# ChameleonMini-RevG.net
KiCad netlist of a schematic drawn in EAGLE
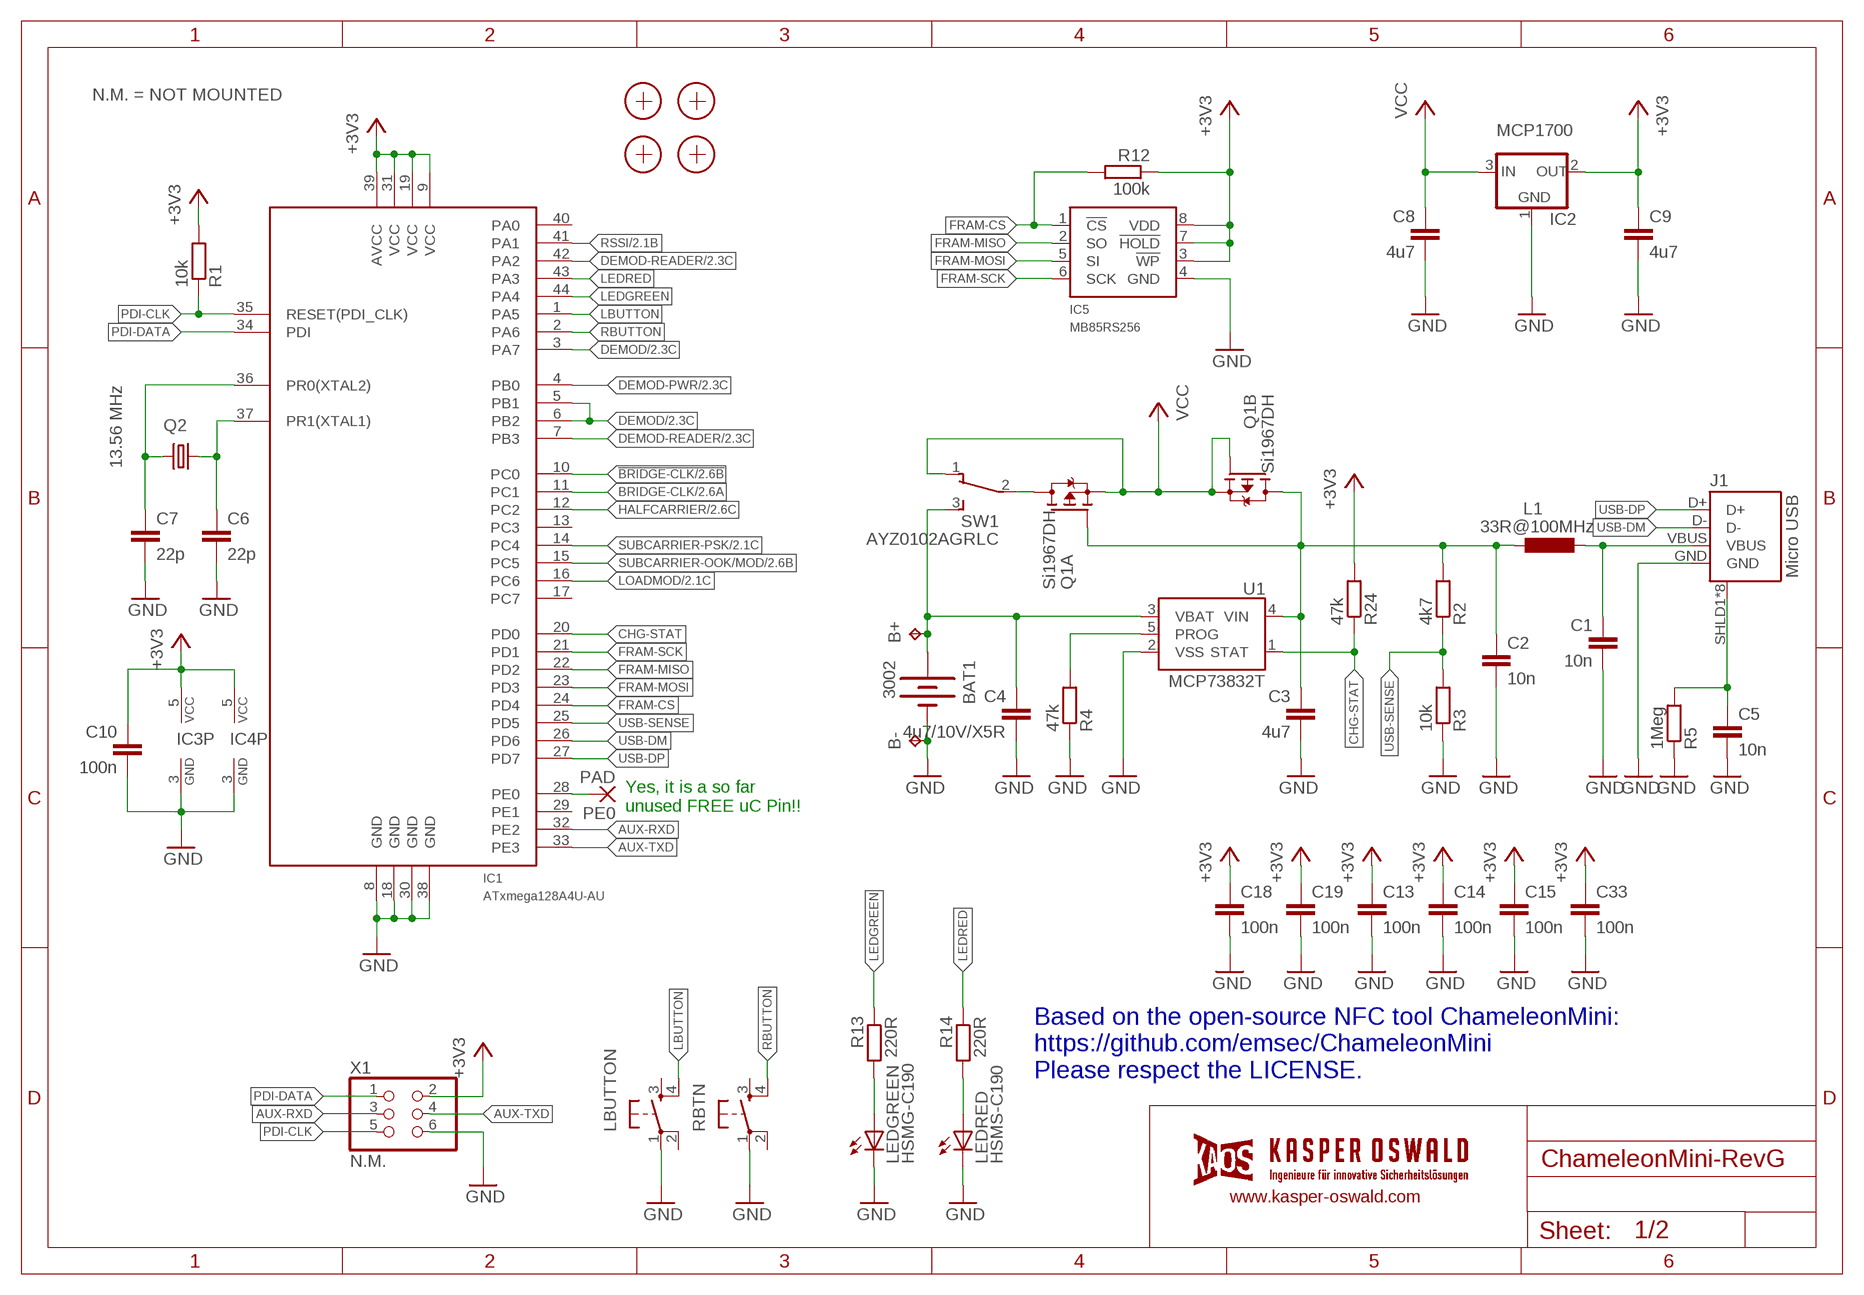
[diagram p0: schematic, sheet 1]
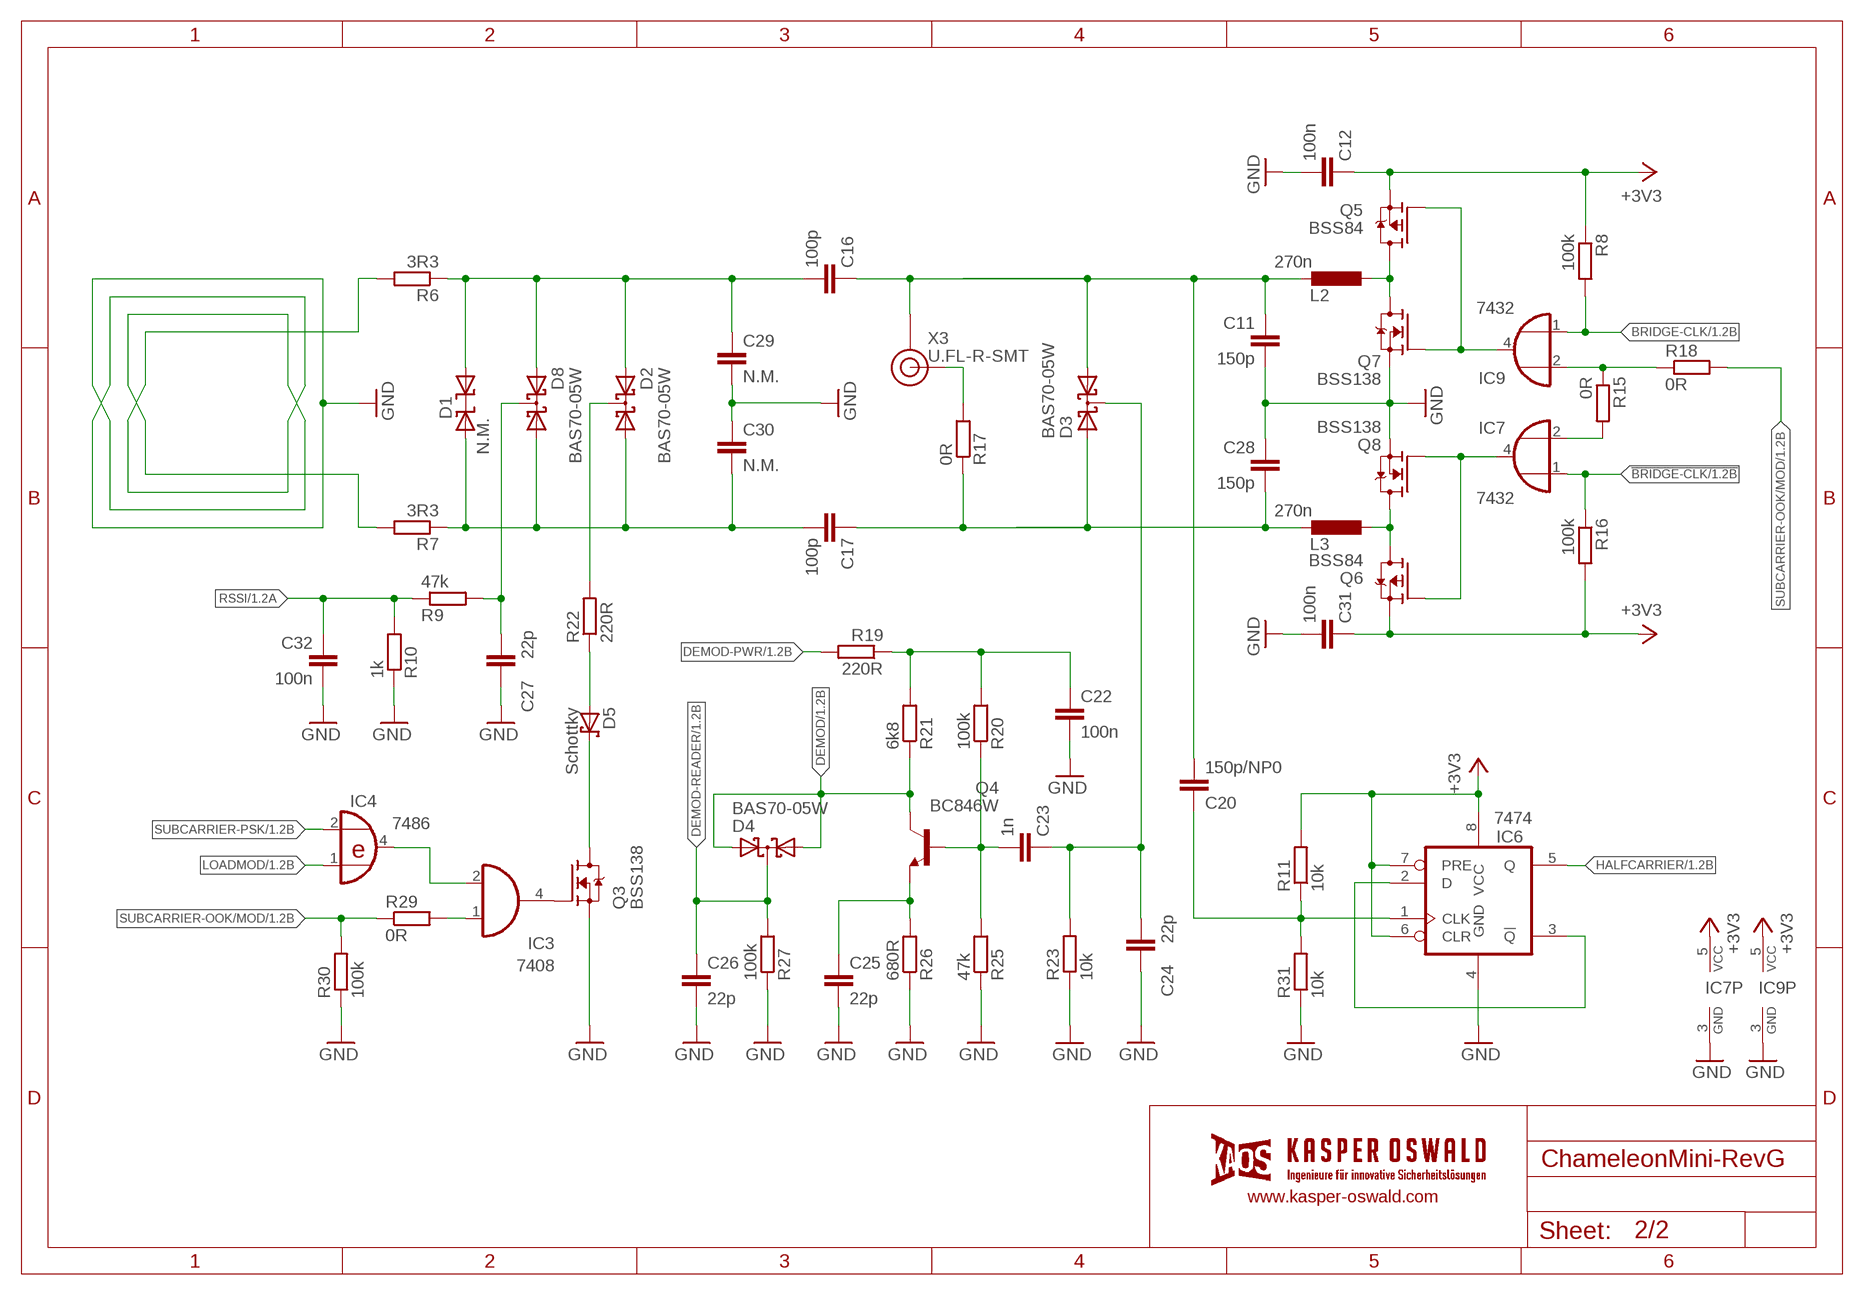
[diagram p1: schematic, sheet 2]

(export (version "E")
  (design (tool "Eeschema 10.0.6"))
  (components
    (comp (ref "C11")
      (value "150p")
      (footprint "eagle-import:C0603K")
      (libsource (lib "eagle-import") (part "C-EUC0603K"))
    )
    (comp (ref "C12")
      (value "100n")
      (footprint "eagle-import:C0603K")
      (libsource (lib "eagle-import") (part "C-EUC0603K"))
    )
    (comp (ref "C16")
      (value "100p")
      (footprint "eagle-import:C0603K")
      (libsource (lib "eagle-import") (part "C-EUC0603K"))
    )
    (comp (ref "C17")
      (value "100p")
      (footprint "eagle-import:C0603K")
      (libsource (lib "eagle-import") (part "C-EUC0603K"))
    )
    (comp (ref "C20")
      (value "150p/NP0")
      (footprint "eagle-import:C0603K")
      (libsource (lib "eagle-import") (part "C-EUC0603K"))
    )
    (comp (ref "C22")
      (value "100n")
      (footprint "eagle-import:C0603K")
      (libsource (lib "eagle-import") (part "C-EUC0603K"))
    )
    (comp (ref "C23")
      (value "1n")
      (footprint "eagle-import:C0603K")
      (libsource (lib "eagle-import") (part "C-EUC0603K"))
    )
    (comp (ref "C24")
      (value "22p")
      (footprint "eagle-import:C0603K")
      (libsource (lib "eagle-import") (part "C-EUC0603K"))
    )
    (comp (ref "C25")
      (value "22p")
      (footprint "eagle-import:C0603K")
      (libsource (lib "eagle-import") (part "C-EUC0603K"))
    )
    (comp (ref "C26")
      (value "22p")
      (footprint "eagle-import:C0603K")
      (libsource (lib "eagle-import") (part "C-EUC0603K"))
    )
    (comp (ref "C27")
      (value "22p")
      (footprint "eagle-import:C0603K")
      (libsource (lib "eagle-import") (part "C-EUC0603K"))
    )
    (comp (ref "C28")
      (value "150p")
      (footprint "eagle-import:C0603K")
      (libsource (lib "eagle-import") (part "C-EUC0603K"))
    )
    (comp (ref "C29")
      (value "N.M.")
      (footprint "eagle-import:C0603K")
      (libsource (lib "eagle-import") (part "C-EUC0603K"))
    )
    (comp (ref "C30")
      (value "N.M.")
      (footprint "eagle-import:C0603K")
      (libsource (lib "eagle-import") (part "C-EUC0603K"))
    )
    (comp (ref "C31")
      (value "100n")
      (footprint "eagle-import:C0603K")
      (libsource (lib "eagle-import") (part "C-EUC0603K"))
    )
    (comp (ref "C32")
      (value "100n")
      (footprint "eagle-import:C0603K")
      (libsource (lib "eagle-import") (part "C-EUC0603K"))
    )
    (comp (ref "D1")
      (value "N.M.")
      (footprint "eagle-import:DO214AC")
      (libsource (lib "eagle-import") (part "SMAJ"))
    )
    (comp (ref "D2")
      (value "BAS70-05W")
      (footprint "eagle-import:SOT323")
      (libsource (lib "eagle-import") (part "BAS70-05W"))
    )
    (comp (ref "D3")
      (value "BAS70-05W")
      (footprint "eagle-import:SOT323")
      (libsource (lib "eagle-import") (part "BAS70-05W"))
    )
    (comp (ref "D4")
      (value "BAS70-05W")
      (footprint "eagle-import:SOT323")
      (libsource (lib "eagle-import") (part "BAS70-05W"))
    )
    (comp (ref "D5")
      (value "Schottky")
      (footprint "eagle-import:SOD323(F)")
      (libsource (lib "eagle-import") (part "1PS76SB70"))
    )
    (comp (ref "D8")
      (value "BAS70-05W")
      (footprint "eagle-import:SOT323")
      (libsource (lib "eagle-import") (part "BAS70-05W"))
    )
    (comp (ref "IC3")
      (value "7408")
      (footprint "eagle-import:SC70-5")
      (libsource (lib "eagle-import") (part "741G08DCKLVC"))
    )
    (comp (ref "IC4")
      (value "7486")
      (footprint "eagle-import:SC70-5")
      (libsource (lib "eagle-import") (part "741G86DCKAHC"))
    )
    (comp (ref "IC6")
      (value "7474")
      (footprint "eagle-import:VSSOP8")
      (libsource (lib "eagle-import") (part "74LVC1G74DC"))
    )
    (comp (ref "IC7")
      (value "7432")
      (footprint "eagle-import:SC70-5")
      (libsource (lib "eagle-import") (part "741G32DCKAHC"))
    )
    (comp (ref "IC9")
      (value "7432")
      (footprint "eagle-import:SC70-5")
      (libsource (lib "eagle-import") (part "741G32DCKAHC"))
    )
    (comp (ref "L2")
      (value "270n")
      (footprint "eagle-import:L2012C")
      (libsource (lib "eagle-import") (part "L-EUL2012C"))
    )
    (comp (ref "L3")
      (value "270n")
      (footprint "eagle-import:L2012C")
      (libsource (lib "eagle-import") (part "L-EUL2012C"))
    )
    (comp (ref "Q3")
      (value "BSS138")
      (footprint "eagle-import:SOT323")
      (libsource (lib "eagle-import") (part "BSS138BKW"))
    )
    (comp (ref "Q4")
      (value "BC846W")
      (footprint "eagle-import:SOT323")
      (libsource (lib "eagle-import") (part "BC84XW"))
    )
    (comp (ref "Q5")
      (value "BSS84")
      (footprint "eagle-import:SOT323")
      (libsource (lib "eagle-import") (part "BSS84AKW"))
    )
    (comp (ref "Q6")
      (value "BSS84")
      (footprint "eagle-import:SOT323")
      (libsource (lib "eagle-import") (part "BSS84AKW"))
    )
    (comp (ref "Q7")
      (value "BSS138")
      (footprint "eagle-import:SOT323")
      (libsource (lib "eagle-import") (part "BSS138BKW"))
    )
    (comp (ref "Q8")
      (value "BSS138")
      (footprint "eagle-import:SOT323")
      (libsource (lib "eagle-import") (part "BSS138BKW"))
    )
    (comp (ref "R6")
      (value "3R3")
      (footprint "eagle-import:R0603")
      (libsource (lib "eagle-import") (part "R-EU_R0603"))
    )
    (comp (ref "R7")
      (value "3R3")
      (footprint "eagle-import:R0603")
      (libsource (lib "eagle-import") (part "R-EU_R0603"))
    )
    (comp (ref "R8")
      (value "100k")
      (footprint "eagle-import:R0603")
      (libsource (lib "eagle-import") (part "R-EU_R0603"))
    )
    (comp (ref "R9")
      (value "47k")
      (footprint "eagle-import:R0603")
      (libsource (lib "eagle-import") (part "R-EU_R0603"))
    )
    (comp (ref "R10")
      (value "1k")
      (footprint "eagle-import:R0603")
      (libsource (lib "eagle-import") (part "R-EU_R0603"))
    )
    (comp (ref "R11")
      (value "10k")
      (footprint "eagle-import:R0603")
      (libsource (lib "eagle-import") (part "R-EU_R0603"))
    )
    (comp (ref "R15")
      (value "0R")
      (footprint "eagle-import:R0603")
      (libsource (lib "eagle-import") (part "R-EU_R0603"))
    )
    (comp (ref "R16")
      (value "100k")
      (footprint "eagle-import:R0603")
      (libsource (lib "eagle-import") (part "R-EU_R0603"))
    )
    (comp (ref "R17")
      (value "0R")
      (footprint "eagle-import:R0603")
      (libsource (lib "eagle-import") (part "R-EU_R0603"))
    )
    (comp (ref "R18")
      (value "0R")
      (footprint "eagle-import:R0603")
      (libsource (lib "eagle-import") (part "R-EU_R0603"))
    )
    (comp (ref "R19")
      (value "220R")
      (footprint "eagle-import:R0603")
      (libsource (lib "eagle-import") (part "R-EU_R0603"))
    )
    (comp (ref "R20")
      (value "100k")
      (footprint "eagle-import:R0603")
      (libsource (lib "eagle-import") (part "R-EU_R0603"))
    )
    (comp (ref "R21")
      (value "6k8")
      (footprint "eagle-import:R0603")
      (libsource (lib "eagle-import") (part "R-EU_R0603"))
    )
    (comp (ref "R22")
      (value "220R")
      (footprint "eagle-import:R0603")
      (libsource (lib "eagle-import") (part "R-EU_R0603"))
    )
    (comp (ref "R23")
      (value "10k")
      (footprint "eagle-import:R0603")
      (libsource (lib "eagle-import") (part "R-EU_R0603"))
    )
    (comp (ref "R25")
      (value "47k")
      (footprint "eagle-import:R0603")
      (libsource (lib "eagle-import") (part "R-EU_R0603"))
    )
    (comp (ref "R26")
      (value "680R")
      (footprint "eagle-import:R0603")
      (libsource (lib "eagle-import") (part "R-EU_R0603"))
    )
    (comp (ref "R27")
      (value "100k")
      (footprint "eagle-import:R0603")
      (libsource (lib "eagle-import") (part "R-EU_R0603"))
    )
    (comp (ref "R29")
      (value "0R")
      (footprint "eagle-import:R0603")
      (libsource (lib "eagle-import") (part "R-EU_R0603"))
    )
    (comp (ref "R30")
      (value "100k")
      (footprint "eagle-import:R0603")
      (libsource (lib "eagle-import") (part "R-EU_R0603"))
    )
    (comp (ref "R31")
      (value "10k")
      (footprint "eagle-import:R0603")
      (libsource (lib "eagle-import") (part "R-EU_R0603"))
    )
    (comp (ref "X3")
      (value "U.FL-R-SMT")
      (footprint "eagle-import:U.FL-R-SMT")
      (libsource (lib "eagle-import") (part "U.FL-R-SMT"))
    )
    (comp (ref "B+")
      (value "TPTP18SQ")
      (footprint "eagle-import:TP18SQ")
      (libsource (lib "eagle-import") (part "TPTP18SQ"))
    )
    (comp (ref "B-")
      (value "TPTP18SQ")
      (footprint "eagle-import:TP18SQ")
      (libsource (lib "eagle-import") (part "TPTP18SQ"))
    )
    (comp (ref "BAT1")
      (value "3002")
      (footprint "eagle-import:BATTCON_20MM")
      (libsource (lib "eagle-import") (part "3002"))
    )
    (comp (ref "C1")
      (value "10n")
      (footprint "eagle-import:C1206K")
      (libsource (lib "eagle-import") (part "C-EUC1206K"))
    )
    (comp (ref "C2")
      (value "10n")
      (footprint "eagle-import:C1206K")
      (libsource (lib "eagle-import") (part "C-EUC1206K"))
    )
    (comp (ref "C3")
      (value "4u7")
      (footprint "eagle-import:C0603K")
      (libsource (lib "eagle-import") (part "C-EUC0603K"))
    )
    (comp (ref "C4")
      (value "4u7/10V/X5R")
      (footprint "eagle-import:C0603K")
      (libsource (lib "eagle-import") (part "C-EUC0603K"))
    )
    (comp (ref "C5")
      (value "10n")
      (footprint "eagle-import:C0603K")
      (libsource (lib "eagle-import") (part "C-EUC0603K"))
    )
    (comp (ref "C6")
      (value "22p")
      (footprint "eagle-import:C0603K")
      (libsource (lib "eagle-import") (part "C-EUC0603K"))
    )
    (comp (ref "C7")
      (value "22p")
      (footprint "eagle-import:C0603K")
      (libsource (lib "eagle-import") (part "C-EUC0603K"))
    )
    (comp (ref "C8")
      (value "4u7")
      (footprint "eagle-import:C0603K")
      (libsource (lib "eagle-import") (part "C-EUC0603K"))
    )
    (comp (ref "C9")
      (value "4u7")
      (footprint "eagle-import:C0603K")
      (libsource (lib "eagle-import") (part "C-EUC0603K"))
    )
    (comp (ref "C10")
      (value "100n")
      (footprint "eagle-import:C0603K")
      (libsource (lib "eagle-import") (part "C-EUC0603K"))
    )
    (comp (ref "C13")
      (value "100n")
      (footprint "eagle-import:C0603K")
      (libsource (lib "eagle-import") (part "C-EUC0603K"))
    )
    (comp (ref "C14")
      (value "100n")
      (footprint "eagle-import:C0603K")
      (libsource (lib "eagle-import") (part "C-EUC0603K"))
    )
    (comp (ref "C15")
      (value "100n")
      (footprint "eagle-import:C0603K")
      (libsource (lib "eagle-import") (part "C-EUC0603K"))
    )
    (comp (ref "C18")
      (value "100n")
      (footprint "eagle-import:C0603K")
      (libsource (lib "eagle-import") (part "C-EUC0603K"))
    )
    (comp (ref "C19")
      (value "100n")
      (footprint "eagle-import:C0603K")
      (libsource (lib "eagle-import") (part "C-EUC0603K"))
    )
    (comp (ref "C33")
      (value "100n")
      (footprint "eagle-import:C0603K")
      (libsource (lib "eagle-import") (part "C-EUC0603K"))
    )
    (comp (ref "IC1")
      (value "ATxmega128A4U-AU")
      (footprint "eagle-import:TQFP44")
      (libsource (lib "eagle-import") (part "ATXMEGA_A4-A"))
    )
    (comp (ref "IC2")
      (value "MCP1700")
      (footprint "eagle-import:SOT23")
      (libsource (lib "eagle-import") (part "MCP1702"))
    )
    (comp (ref "IC5")
      (value "MB85RS256")
      (footprint "eagle-import:SO-08")
      (libsource (lib "eagle-import") (part "MB85RS"))
    )
    (comp (ref "J1")
      (value "Micro USB")
      (footprint "eagle-import:USB-MICROB-10118194")
      (libsource (lib "eagle-import") (part "USB-MICROB-2"))
    )
    (comp (ref "L1")
      (value "33R@100MHz")
      (footprint "eagle-import:L2012C")
      (libsource (lib "eagle-import") (part "L-EUL2012C"))
    )
    (comp (ref "LBUTTON")
      (value "SWITCH_SPST_4_PINSQUARE")
      (footprint "eagle-import:TACTILE-SWITCH-SMD")
      (libsource (lib "eagle-import") (part "SWITCH_SPST_4_PINSQUARE"))
    )
    (comp (ref "LEDGREEN")
      (value "HSMG-C190")
      (footprint "eagle-import:CHIPLED-0603")
      (libsource (lib "eagle-import") (part "LED-0603"))
    )
    (comp (ref "LEDRED")
      (value "HSMS-C190")
      (footprint "eagle-import:CHIPLED-0603")
      (libsource (lib "eagle-import") (part "LED-0603"))
    )
    (comp (ref "PE0")
      (value "PAD")
      (footprint "eagle-import:SMD1,27-2,54")
      (libsource (lib "eagle-import") (part "WIREPADSMD1,27-254"))
    )
    (comp (ref "Q1")
      (value "Si1967DH")
      (footprint "eagle-import:SOT363")
      (libsource (lib "eagle-import") (part "BSS84AKS"))
    )
    (comp (ref "Q2")
      (value "13.56 MHz")
      (footprint "eagle-import:5MMX3.2MM")
      (libsource (lib "eagle-import") (part "TXC7B"))
    )
    (comp (ref "R1")
      (value "10k")
      (footprint "eagle-import:R0603")
      (libsource (lib "eagle-import") (part "R-EU_R0603"))
    )
    (comp (ref "R2")
      (value "4k7")
      (footprint "eagle-import:R0603")
      (libsource (lib "eagle-import") (part "R-EU_R0603"))
    )
    (comp (ref "R3")
      (value "10k")
      (footprint "eagle-import:R0603")
      (libsource (lib "eagle-import") (part "R-EU_R0603"))
    )
    (comp (ref "R4")
      (value "47k")
      (footprint "eagle-import:R0603")
      (libsource (lib "eagle-import") (part "R-EU_R0603"))
    )
    (comp (ref "R5")
      (value "1Meg")
      (footprint "eagle-import:R0603")
      (libsource (lib "eagle-import") (part "R-EU_R0603"))
    )
    (comp (ref "R12")
      (value "100k")
      (footprint "eagle-import:R0603")
      (libsource (lib "eagle-import") (part "R-EU_R0603"))
    )
    (comp (ref "R13")
      (value "220R")
      (footprint "eagle-import:R0603")
      (libsource (lib "eagle-import") (part "R-EU_R0603"))
    )
    (comp (ref "R14")
      (value "220R")
      (footprint "eagle-import:R0603")
      (libsource (lib "eagle-import") (part "R-EU_R0603"))
    )
    (comp (ref "R24")
      (value "47k")
      (footprint "eagle-import:R0603")
      (libsource (lib "eagle-import") (part "R-EU_R0603"))
    )
    (comp (ref "RBTN")
      (value "SWITCH_SPST_4_PINSQUARE")
      (footprint "eagle-import:TACTILE-SWITCH-SMD")
      (libsource (lib "eagle-import") (part "SWITCH_SPST_4_PINSQUARE"))
    )
    (comp (ref "SW1")
      (value "AYZ0102AGRLC")
      (footprint "eagle-import:AYZ0102AGRLC")
      (libsource (lib "eagle-import") (part "AYZ0102AGRLC"))
    )
    (comp (ref "U1")
      (value "MCP73832T")
      (footprint "eagle-import:SOT23-5")
      (libsource (lib "eagle-import") (part "MCP73831"))
    )
    (comp (ref "X1")
      (value "N.M.")
      (footprint "eagle-import:PINHD-2X3-2.54-EDGE")
      (libsource (lib "eagle-import") (part "PINHD-2X3-2.54-EDGE"))
    )
    (comp (ref "X2")
      (value "PASSER-07")
      (footprint "eagle-import:PASSER_07MM")
      (libsource (lib "eagle-import") (part "PASSER-07"))
    )
    (comp (ref "X4")
      (value "PASSER-07")
      (footprint "eagle-import:PASSER_07MM")
      (libsource (lib "eagle-import") (part "PASSER-07"))
    )
    (comp (ref "X5")
      (value "PASSER-07")
      (footprint "eagle-import:PASSER_07MM")
      (libsource (lib "eagle-import") (part "PASSER-07"))
    )
    (comp (ref "X6")
      (value "PASSER-07")
      (footprint "eagle-import:PASSER_07MM")
      (libsource (lib "eagle-import") (part "PASSER-07"))
    )
  )
  (nets
    (net (code "1") (name "+3V3") (class "Default")
      (node (ref "C10") (pin "1") (pinfunction "1_1") (pintype "passive"))
      (node (ref "C12") (pin "1") (pinfunction "1_1") (pintype "passive"))
      (node (ref "C13") (pin "1") (pinfunction "1_1") (pintype "passive"))
      (node (ref "C14") (pin "1") (pinfunction "1_1") (pintype "passive"))
      (node (ref "C15") (pin "1") (pinfunction "1_1") (pintype "passive"))
      (node (ref "C18") (pin "1") (pinfunction "1_1") (pintype "passive"))
      (node (ref "C19") (pin "1") (pinfunction "1_1") (pintype "passive"))
      (node (ref "C31") (pin "1") (pinfunction "1_1") (pintype "passive"))
      (node (ref "C33") (pin "1") (pinfunction "1_1") (pintype "passive"))
      (node (ref "C9") (pin "1") (pinfunction "1_1") (pintype "passive"))
      (node (ref "IC1") (pin "19") (pinfunction "VCC_19") (pintype "bidirectional"))
      (node (ref "IC1") (pin "31") (pinfunction "VCC_31") (pintype "bidirectional"))
      (node (ref "IC1") (pin "39") (pinfunction "AVCC_39") (pintype "bidirectional"))
      (node (ref "IC1") (pin "9") (pinfunction "VCC_9") (pintype "bidirectional"))
      (node (ref "IC2") (pin "2") (pinfunction "OUT_2") (pintype "passive"))
      (node (ref "IC3") (pin "5") (pinfunction "VCC_5") (pintype "power_in"))
      (node (ref "IC4") (pin "5") (pinfunction "VCC_5") (pintype "power_in"))
      (node (ref "IC5") (pin "3") (pinfunction "~{WP}_3") (pintype "bidirectional"))
      (node (ref "IC5") (pin "7") (pinfunction "~{HOLD}_7") (pintype "bidirectional"))
      (node (ref "IC5") (pin "8") (pinfunction "VDD_8") (pintype "bidirectional"))
      (node (ref "IC6") (pin "6") (pinfunction "CLR_6") (pintype "input"))
      (node (ref "IC6") (pin "7") (pinfunction "PRE_7") (pintype "input"))
      (node (ref "IC6") (pin "8") (pinfunction "VCC_8") (pintype "bidirectional"))
      (node (ref "IC7") (pin "5") (pinfunction "VCC_5") (pintype "power_in"))
      (node (ref "IC9") (pin "5") (pinfunction "VCC_5") (pintype "power_in"))
      (node (ref "Q5") (pin "2") (pinfunction "S_2") (pintype "passive"))
      (node (ref "Q6") (pin "2") (pinfunction "S_2") (pintype "passive"))
      (node (ref "R1") (pin "2") (pinfunction "2_2") (pintype "passive"))
      (node (ref "R11") (pin "2") (pinfunction "2_2") (pintype "passive"))
      (node (ref "R12") (pin "1") (pinfunction "1_1") (pintype "passive"))
      (node (ref "R16") (pin "2") (pinfunction "2_2") (pintype "passive"))
      (node (ref "R24") (pin "2") (pinfunction "2_2") (pintype "passive"))
      (node (ref "R8") (pin "1") (pinfunction "1_1") (pintype "passive"))
      (node (ref "X1") (pin "2") (pinfunction "2_2") (pintype "passive"))
    )
    (net (code "2") (name "AUX-RXD") (class "Default")
      (node (ref "IC1") (pin "32") (pinfunction "PE2_32") (pintype "bidirectional"))
      (node (ref "X1") (pin "3") (pinfunction "3_3") (pintype "passive"))
    )
    (net (code "3") (name "AUX-TXD") (class "Default")
      (node (ref "IC1") (pin "33") (pinfunction "PE3_33") (pintype "bidirectional"))
      (node (ref "X1") (pin "4") (pinfunction "4_4") (pintype "passive"))
    )
    (net (code "4") (name "BRIDGE-CLK") (class "Default")
      (node (ref "IC1") (pin "11") (pinfunction "PC1_11") (pintype "bidirectional"))
      (node (ref "IC9") (pin "1") (pinfunction "I0_1") (pintype "input"))
      (node (ref "R8") (pin "2") (pinfunction "2_2") (pintype "passive"))
    )
    (net (code "5") (name "CHG-STAT") (class "Default")
      (node (ref "IC1") (pin "20") (pinfunction "PD0_20") (pintype "bidirectional"))
      (node (ref "R24") (pin "1") (pinfunction "1_1") (pintype "passive"))
      (node (ref "U1") (pin "1") (pinfunction "STAT_1") (pintype "output"))
    )
    (net (code "6") (name "DEMOD") (class "Default")
      (node (ref "D4") (pin "1") (pinfunction "A1_1") (pintype "passive"))
      (node (ref "D4") (pin "2") (pinfunction "A2_2") (pintype "passive"))
      (node (ref "IC1") (pin "3") (pinfunction "PA7_3") (pintype "bidirectional"))
      (node (ref "IC1") (pin "5") (pinfunction "PB1_5") (pintype "bidirectional"))
      (node (ref "IC1") (pin "6") (pinfunction "PB2_6") (pintype "bidirectional"))
      (node (ref "Q4") (pin "3") (pinfunction "C_3") (pintype "passive"))
      (node (ref "R21") (pin "1") (pinfunction "1_1") (pintype "passive"))
    )
    (net (code "7") (name "DEMOD-PWR") (class "Default")
      (node (ref "IC1") (pin "4") (pinfunction "PB0_4") (pintype "bidirectional"))
      (node (ref "R19") (pin "2") (pinfunction "2_2") (pintype "passive"))
    )
    (net (code "8") (name "DEMOD-READER") (class "Default")
      (node (ref "C26") (pin "1") (pinfunction "1_1") (pintype "passive"))
      (node (ref "D4") (pin "3") (pinfunction "K_3") (pintype "passive"))
      (node (ref "IC1") (pin "42") (pinfunction "PA2_42") (pintype "bidirectional"))
      (node (ref "IC1") (pin "7") (pinfunction "PB3_7") (pintype "bidirectional"))
      (node (ref "R27") (pin "2") (pinfunction "2_2") (pintype "passive"))
    )
    (net (code "9") (name "FRAM-CS") (class "Default")
      (node (ref "IC1") (pin "24") (pinfunction "PD4_24") (pintype "bidirectional"))
      (node (ref "IC5") (pin "1") (pinfunction "~{CS}_1") (pintype "bidirectional"))
      (node (ref "R12") (pin "2") (pinfunction "2_2") (pintype "passive"))
    )
    (net (code "10") (name "FRAM-MISO") (class "Default")
      (node (ref "IC1") (pin "22") (pinfunction "PD2_22") (pintype "bidirectional"))
      (node (ref "IC5") (pin "2") (pinfunction "SO_2") (pintype "bidirectional"))
    )
    (net (code "11") (name "FRAM-MOSI") (class "Default")
      (node (ref "IC1") (pin "23") (pinfunction "PD3_23") (pintype "bidirectional"))
      (node (ref "IC5") (pin "5") (pinfunction "SI_5") (pintype "bidirectional"))
    )
    (net (code "12") (name "FRAM-SCK") (class "Default")
      (node (ref "IC1") (pin "21") (pinfunction "PD1_21") (pintype "bidirectional"))
      (node (ref "IC5") (pin "6") (pinfunction "SCK_6") (pintype "bidirectional"))
    )
    (net (code "13") (name "GND") (class "Default")
      (node (ref "B-") (pin "TP") (pinfunction "TP_TP") (pintype "input"))
      (node (ref "BAT1") (pin "-") (pinfunction "-_-") (pintype "power_in"))
      (node (ref "C1") (pin "2") (pinfunction "2_2") (pintype "passive"))
      (node (ref "C10") (pin "2") (pinfunction "2_2") (pintype "passive"))
      (node (ref "C11") (pin "2") (pinfunction "2_2") (pintype "passive"))
      (node (ref "C12") (pin "2") (pinfunction "2_2") (pintype "passive"))
      (node (ref "C13") (pin "2") (pinfunction "2_2") (pintype "passive"))
      (node (ref "C14") (pin "2") (pinfunction "2_2") (pintype "passive"))
      (node (ref "C15") (pin "2") (pinfunction "2_2") (pintype "passive"))
      (node (ref "C18") (pin "2") (pinfunction "2_2") (pintype "passive"))
      (node (ref "C19") (pin "2") (pinfunction "2_2") (pintype "passive"))
      (node (ref "C2") (pin "2") (pinfunction "2_2") (pintype "passive"))
      (node (ref "C22") (pin "2") (pinfunction "2_2") (pintype "passive"))
      (node (ref "C24") (pin "2") (pinfunction "2_2") (pintype "passive"))
      (node (ref "C25") (pin "2") (pinfunction "2_2") (pintype "passive"))
      (node (ref "C26") (pin "2") (pinfunction "2_2") (pintype "passive"))
      (node (ref "C27") (pin "2") (pinfunction "2_2") (pintype "passive"))
      (node (ref "C28") (pin "1") (pinfunction "1_1") (pintype "passive"))
      (node (ref "C29") (pin "2") (pinfunction "2_2") (pintype "passive"))
      (node (ref "C3") (pin "2") (pinfunction "2_2") (pintype "passive"))
      (node (ref "C30") (pin "1") (pinfunction "1_1") (pintype "passive"))
      (node (ref "C31") (pin "2") (pinfunction "2_2") (pintype "passive"))
      (node (ref "C32") (pin "2") (pinfunction "2_2") (pintype "passive"))
      (node (ref "C33") (pin "2") (pinfunction "2_2") (pintype "passive"))
      (node (ref "C4") (pin "2") (pinfunction "2_2") (pintype "passive"))
      (node (ref "C5") (pin "2") (pinfunction "2_2") (pintype "passive"))
      (node (ref "C6") (pin "2") (pinfunction "2_2") (pintype "passive"))
      (node (ref "C7") (pin "2") (pinfunction "2_2") (pintype "passive"))
      (node (ref "C8") (pin "2") (pinfunction "2_2") (pintype "passive"))
      (node (ref "C9") (pin "2") (pinfunction "2_2") (pintype "passive"))
      (node (ref "IC1") (pin "18") (pinfunction "GND_18") (pintype "bidirectional"))
      (node (ref "IC1") (pin "30") (pinfunction "GND_30") (pintype "bidirectional"))
      (node (ref "IC1") (pin "38") (pinfunction "GND_38") (pintype "bidirectional"))
      (node (ref "IC1") (pin "8") (pinfunction "GND_8") (pintype "bidirectional"))
      (node (ref "IC2") (pin "1") (pinfunction "GND_1") (pintype "input"))
      (node (ref "IC3") (pin "3") (pinfunction "GND_3") (pintype "power_in"))
      (node (ref "IC4") (pin "3") (pinfunction "GND_3") (pintype "power_in"))
      (node (ref "IC5") (pin "4") (pinfunction "GND_4") (pintype "bidirectional"))
      (node (ref "IC6") (pin "4") (pinfunction "GND_4") (pintype "bidirectional"))
      (node (ref "IC7") (pin "3") (pinfunction "GND_3") (pintype "power_in"))
      (node (ref "IC9") (pin "3") (pinfunction "GND_3") (pintype "power_in"))
      (node (ref "J1") (pin "GND") (pinfunction "GND_GND") (pintype "power_in"))
      (node (ref "LBUTTON") (pin "1") (pinfunction "1_1") (pintype "passive"))
      (node (ref "LEDGREEN") (pin "C") (pinfunction "C_C") (pintype "passive"))
      (node (ref "LEDRED") (pin "C") (pinfunction "C_C") (pintype "passive"))
      (node (ref "Q3") (pin "2") (pinfunction "S_2") (pintype "passive"))
      (node (ref "Q7") (pin "2") (pinfunction "S_2") (pintype "passive"))
      (node (ref "Q8") (pin "2") (pinfunction "S_2") (pintype "passive"))
      (node (ref "R10") (pin "1") (pinfunction "1_1") (pintype "passive"))
      (node (ref "R23") (pin "1") (pinfunction "1_1") (pintype "passive"))
      (node (ref "R25") (pin "1") (pinfunction "1_1") (pintype "passive"))
      (node (ref "R26") (pin "1") (pinfunction "1_1") (pintype "passive"))
      (node (ref "R27") (pin "1") (pinfunction "1_1") (pintype "passive"))
      (node (ref "R3") (pin "1") (pinfunction "1_1") (pintype "passive"))
      (node (ref "R30") (pin "1") (pinfunction "1_1") (pintype "passive"))
      (node (ref "R31") (pin "1") (pinfunction "1_1") (pintype "passive"))
      (node (ref "R4") (pin "1") (pinfunction "1_1") (pintype "passive"))
      (node (ref "R5") (pin "1") (pinfunction "1_1") (pintype "passive"))
      (node (ref "R6") (pin "2") (pinfunction "2_2") (pintype "passive"))
      (node (ref "R7") (pin "2") (pinfunction "2_2") (pintype "passive"))
      (node (ref "RBTN") (pin "1") (pinfunction "1_1") (pintype "passive"))
      (node (ref "U1") (pin "2") (pinfunction "VSS_2") (pintype "power_in"))
      (node (ref "X1") (pin "6") (pinfunction "6_6") (pintype "passive"))
    )
    (net (code "14") (name "HALFCARRIER") (class "Default")
      (node (ref "IC1") (pin "12") (pinfunction "PC2_12") (pintype "bidirectional"))
      (node (ref "IC6") (pin "5") (pinfunction "Q_5") (pintype "output"))
    )
    (net (code "15") (name "LBUTTON") (class "Default")
      (node (ref "IC1") (pin "1") (pinfunction "PA5_1") (pintype "bidirectional"))
      (node (ref "LBUTTON") (pin "4") (pinfunction "4_4") (pintype "passive"))
    )
    (net (code "16") (name "LEDGREEN") (class "Default")
      (node (ref "IC1") (pin "44") (pinfunction "PA4_44") (pintype "bidirectional"))
      (node (ref "R13") (pin "1") (pinfunction "1_1") (pintype "passive"))
    )
    (net (code "17") (name "LEDRED") (class "Default")
      (node (ref "IC1") (pin "43") (pinfunction "PA3_43") (pintype "bidirectional"))
      (node (ref "R14") (pin "1") (pinfunction "1_1") (pintype "passive"))
    )
    (net (code "18") (name "LOADMOD") (class "Default")
      (node (ref "IC1") (pin "16") (pinfunction "PC6_16") (pintype "bidirectional"))
      (node (ref "IC4") (pin "1") (pinfunction "I0_1") (pintype "input"))
    )
    (net (code "19") (name "Net-(BAT1-+)") (class "Default")
      (node (ref "B+") (pin "TP") (pinfunction "TP_TP") (pintype "input"))
      (node (ref "BAT1") (pin "+2") (pinfunction "+_+2") (pintype "power_in"))
      (node (ref "C4") (pin "1") (pinfunction "1_1") (pintype "passive"))
      (node (ref "SW1") (pin "3") (pinfunction "S_3") (pintype "passive"))
      (node (ref "U1") (pin "3") (pinfunction "VBAT_3") (pintype "power_in"))
    )
    (net (code "20") (name "Net-(C1-Pad1)") (class "Default")
      (node (ref "C1") (pin "1") (pinfunction "1_1") (pintype "passive"))
      (node (ref "J1") (pin "VBUS") (pinfunction "VBUS_VBUS") (pintype "power_in"))
      (node (ref "L1") (pin "1") (pinfunction "1_1") (pintype "passive"))
    )
    (net (code "21") (name "Net-(C5-Pad1)") (class "Default")
      (node (ref "C5") (pin "1") (pinfunction "1_1") (pintype "passive"))
      (node (ref "J1") (pin "SHLD1") (pinfunction "SHIELD_SHLD1") (pintype "passive"))
      (node (ref "J1") (pin "SHLD2") (pinfunction "SHIELD_SHLD2") (pintype "passive"))
      (node (ref "J1") (pin "SHLD3") (pinfunction "SHIELD_SHLD3") (pintype "passive"))
      (node (ref "J1") (pin "SHLD4") (pinfunction "SHIELD_SHLD4") (pintype "passive"))
      (node (ref "J1") (pin "SHLD5") (pinfunction "SHIELD_SHLD5") (pintype "passive"))
      (node (ref "J1") (pin "SHLD6") (pinfunction "SHIELD_SHLD6") (pintype "passive"))
      (node (ref "J1") (pin "SHLD7") (pinfunction "SHIELD_SHLD7") (pintype "passive"))
      (node (ref "J1") (pin "SHLD8") (pinfunction "SHIELD_SHLD8") (pintype "passive"))
      (node (ref "R5") (pin "2") (pinfunction "2_2") (pintype "passive"))
    )
    (net (code "22") (name "Net-(C22-Pad1)") (class "Default")
      (node (ref "C22") (pin "1") (pinfunction "1_1") (pintype "passive"))
      (node (ref "R19") (pin "1") (pinfunction "1_1") (pintype "passive"))
      (node (ref "R20") (pin "2") (pinfunction "2_2") (pintype "passive"))
      (node (ref "R21") (pin "2") (pinfunction "2_2") (pintype "passive"))
    )
    (net (code "23") (name "Net-(D2-A1)") (class "Default")
      (node (ref "C16") (pin "2") (pinfunction "2_2") (pintype "passive"))
      (node (ref "C29") (pin "1") (pinfunction "1_1") (pintype "passive"))
      (node (ref "D1") (pin "2") (pinfunction "2_2") (pintype "passive"))
      (node (ref "D2") (pin "1") (pinfunction "A1_1") (pintype "passive"))
      (node (ref "D8") (pin "1") (pinfunction "A1_1") (pintype "passive"))
      (node (ref "R6") (pin "1") (pinfunction "1_1") (pintype "passive"))
    )
    (net (code "24") (name "Net-(D2-A2)") (class "Default")
      (node (ref "C17") (pin "2") (pinfunction "2_2") (pintype "passive"))
      (node (ref "C30") (pin "2") (pinfunction "2_2") (pintype "passive"))
      (node (ref "D1") (pin "1") (pinfunction "1_1") (pintype "passive"))
      (node (ref "D2") (pin "2") (pinfunction "A2_2") (pintype "passive"))
      (node (ref "D8") (pin "2") (pinfunction "A2_2") (pintype "passive"))
      (node (ref "R7") (pin "1") (pinfunction "1_1") (pintype "passive"))
    )
    (net (code "25") (name "Net-(D2-K)") (class "Default")
      (node (ref "D2") (pin "3") (pinfunction "K_3") (pintype "passive"))
      (node (ref "R22") (pin "2") (pinfunction "2_2") (pintype "passive"))
    )
    (net (code "26") (name "Net-(D3-A1)") (class "Default")
      (node (ref "C17") (pin "1") (pinfunction "1_1") (pintype "passive"))
      (node (ref "C28") (pin "2") (pinfunction "2_2") (pintype "passive"))
      (node (ref "D3") (pin "1") (pinfunction "A1_1") (pintype "passive"))
      (node (ref "L3") (pin "2") (pinfunction "2_2") (pintype "passive"))
      (node (ref "R17") (pin "1") (pinfunction "1_1") (pintype "passive"))
    )
    (net (code "27") (name "Net-(D3-A2)") (class "Default")
      (node (ref "C11") (pin "1") (pinfunction "1_1") (pintype "passive"))
      (node (ref "C16") (pin "1") (pinfunction "1_1") (pintype "passive"))
      (node (ref "C20") (pin "2") (pinfunction "2_2") (pintype "passive"))
      (node (ref "D3") (pin "2") (pinfunction "A2_2") (pintype "passive"))
      (node (ref "L2") (pin "2") (pinfunction "2_2") (pintype "passive"))
      (node (ref "X3") (pin "GND1") (pinfunction "GND_GND1") (pintype "bidirectional"))
    )
    (net (code "28") (name "Net-(D3-K)") (class "Default")
      (node (ref "C23") (pin "1") (pinfunction "1_1") (pintype "passive"))
      (node (ref "C24") (pin "1") (pinfunction "1_1") (pintype "passive"))
      (node (ref "D3") (pin "3") (pinfunction "K_3") (pintype "passive"))
      (node (ref "R23") (pin "2") (pinfunction "2_2") (pintype "passive"))
    )
    (net (code "29") (name "Net-(D5-A)") (class "Default")
      (node (ref "D5") (pin "2") (pinfunction "A_2") (pintype "passive"))
      (node (ref "R22") (pin "1") (pinfunction "1_1") (pintype "passive"))
    )
    (net (code "30") (name "Net-(D5-K)") (class "Default")
      (node (ref "D5") (pin "1") (pinfunction "K_1") (pintype "passive"))
      (node (ref "Q3") (pin "3") (pinfunction "D_3") (pintype "passive"))
    )
    (net (code "31") (name "Net-(D8-K)") (class "Default")
      (node (ref "C27") (pin "1") (pinfunction "1_1") (pintype "passive"))
      (node (ref "D8") (pin "3") (pinfunction "K_3") (pintype "passive"))
      (node (ref "R9") (pin "2") (pinfunction "2_2") (pintype "passive"))
    )
    (net (code "32") (name "Net-(IC1-PE0)") (class "Default")
      (node (ref "IC1") (pin "28") (pinfunction "PE0_28") (pintype "bidirectional"))
      (node (ref "PE0") (pin "1") (pinfunction "P_1") (pintype "passive"))
    )
    (net (code "33") (name "Net-(IC1-PR0(XTAL2))") (class "Default")
      (node (ref "C7") (pin "1") (pinfunction "1_1") (pintype "passive"))
      (node (ref "IC1") (pin "36") (pinfunction "PR0(XTAL2)_36") (pintype "bidirectional"))
      (node (ref "Q2") (pin "3") (pinfunction "2_3") (pintype "passive"))
    )
    (net (code "34") (name "Net-(IC1-PR1(XTAL1))") (class "Default")
      (node (ref "C6") (pin "1") (pinfunction "1_1") (pintype "passive"))
      (node (ref "IC1") (pin "37") (pinfunction "PR1(XTAL1)_37") (pintype "bidirectional"))
      (node (ref "Q2") (pin "1") (pinfunction "1_1") (pintype "passive"))
    )
    (net (code "35") (name "Net-(IC3A-I0)") (class "Default")
      (node (ref "IC3") (pin "1") (pinfunction "I0_1") (pintype "input"))
      (node (ref "R29") (pin "2") (pinfunction "2_2") (pintype "passive"))
    )
    (net (code "36") (name "Net-(IC3A-I1)") (class "Default")
      (node (ref "IC3") (pin "2") (pinfunction "I1_2") (pintype "input"))
      (node (ref "IC4") (pin "4") (pinfunction "O_4") (pintype "output"))
    )
    (net (code "37") (name "Net-(IC3A-O)") (class "Default")
      (node (ref "IC3") (pin "4") (pinfunction "O_4") (pintype "output"))
      (node (ref "Q3") (pin "1") (pinfunction "G_1") (pintype "passive"))
    )
    (net (code "38") (name "Net-(IC6-CLK)") (class "Default")
      (node (ref "C20") (pin "1") (pinfunction "1_1") (pintype "passive"))
      (node (ref "IC6") (pin "1") (pinfunction "CLK_1") (pintype "input"))
      (node (ref "R11") (pin "1") (pinfunction "1_1") (pintype "passive"))
      (node (ref "R31") (pin "2") (pinfunction "2_2") (pintype "passive"))
    )
    (net (code "39") (name "Net-(IC6-D)") (class "Default")
      (node (ref "IC6") (pin "2") (pinfunction "D_2") (pintype "input"))
      (node (ref "IC6") (pin "3") (pinfunction "~{Q}_3") (pintype "output"))
    )
    (net (code "40") (name "Net-(IC7A-I1)") (class "Default")
      (node (ref "IC7") (pin "2") (pinfunction "I1_2") (pintype "input"))
      (node (ref "R15") (pin "2") (pinfunction "2_2") (pintype "passive"))
    )
    (net (code "41") (name "Net-(IC7A-O)") (class "Default")
      (node (ref "IC7") (pin "4") (pinfunction "O_4") (pintype "output"))
      (node (ref "Q6") (pin "1") (pinfunction "G_1") (pintype "passive"))
      (node (ref "Q8") (pin "1") (pinfunction "G_1") (pintype "passive"))
    )
    (net (code "42") (name "Net-(IC9A-I1)") (class "Default")
      (node (ref "IC9") (pin "2") (pinfunction "I1_2") (pintype "input"))
      (node (ref "R15") (pin "1") (pinfunction "1_1") (pintype "passive"))
      (node (ref "R18") (pin "1") (pinfunction "1_1") (pintype "passive"))
    )
    (net (code "43") (name "Net-(IC9A-O)") (class "Default")
      (node (ref "IC9") (pin "4") (pinfunction "O_4") (pintype "output"))
      (node (ref "Q5") (pin "1") (pinfunction "G_1") (pintype "passive"))
      (node (ref "Q7") (pin "1") (pinfunction "G_1") (pintype "passive"))
    )
    (net (code "44") (name "Net-(LEDGREEN-PadA)") (class "Default")
      (node (ref "LEDGREEN") (pin "A") (pinfunction "A_A") (pintype "passive"))
      (node (ref "R13") (pin "2") (pinfunction "2_2") (pintype "passive"))
    )
    (net (code "45") (name "Net-(LEDRED-PadA)") (class "Default")
      (node (ref "LEDRED") (pin "A") (pinfunction "A_A") (pintype "passive"))
      (node (ref "R14") (pin "2") (pinfunction "2_2") (pintype "passive"))
    )
    (net (code "46") (name "Net-(Q1A-D)") (class "Default")
      (node (ref "Q1") (pin "6") (pinfunction "D_6") (pintype "passive"))
      (node (ref "SW1") (pin "2") (pinfunction "P_2") (pintype "passive"))
    )
    (net (code "47") (name "Net-(Q1A-G)") (class "Default")
      (node (ref "C2") (pin "1") (pinfunction "1_1") (pintype "passive"))
      (node (ref "C3") (pin "1") (pinfunction "1_1") (pintype "passive"))
      (node (ref "L1") (pin "2") (pinfunction "2_2") (pintype "passive"))
      (node (ref "Q1") (pin "2") (pinfunction "G_2") (pintype "passive"))
      (node (ref "Q1") (pin "3") (pinfunction "D_3") (pintype "passive"))
      (node (ref "R2") (pin "2") (pinfunction "2_2") (pintype "passive"))
      (node (ref "U1") (pin "4") (pinfunction "VIN_4") (pintype "power_in"))
    )
    (net (code "48") (name "Net-(Q4-B)") (class "Default")
      (node (ref "C23") (pin "2") (pinfunction "2_2") (pintype "passive"))
      (node (ref "Q4") (pin "1") (pinfunction "B_1") (pintype "passive"))
      (node (ref "R20") (pin "1") (pinfunction "1_1") (pintype "passive"))
      (node (ref "R25") (pin "2") (pinfunction "2_2") (pintype "passive"))
    )
    (net (code "49") (name "Net-(Q4-E)") (class "Default")
      (node (ref "C25") (pin "1") (pinfunction "1_1") (pintype "passive"))
      (node (ref "Q4") (pin "2") (pinfunction "E_2") (pintype "passive"))
      (node (ref "R26") (pin "2") (pinfunction "2_2") (pintype "passive"))
    )
    (net (code "50") (name "Net-(Q5-D)") (class "Default")
      (node (ref "L2") (pin "1") (pinfunction "1_1") (pintype "passive"))
      (node (ref "Q5") (pin "3") (pinfunction "D_3") (pintype "passive"))
      (node (ref "Q7") (pin "3") (pinfunction "D_3") (pintype "passive"))
    )
    (net (code "51") (name "Net-(Q6-D)") (class "Default")
      (node (ref "L3") (pin "1") (pinfunction "1_1") (pintype "passive"))
      (node (ref "Q6") (pin "3") (pinfunction "D_3") (pintype "passive"))
      (node (ref "Q8") (pin "3") (pinfunction "D_3") (pintype "passive"))
    )
    (net (code "52") (name "Net-(R17-Pad2)") (class "Default")
      (node (ref "R17") (pin "2") (pinfunction "2_2") (pintype "passive"))
      (node (ref "X3") (pin "SIG") (pinfunction "SIG_SIG") (pintype "bidirectional"))
    )
    (net (code "53") (name "Net-(U1-PROG)") (class "Default")
      (node (ref "R4") (pin "2") (pinfunction "2_2") (pintype "passive"))
      (node (ref "U1") (pin "5") (pinfunction "PROG_5") (pintype "input"))
    )
    (net (code "54") (name "PDI-CLK") (class "Default")
      (node (ref "IC1") (pin "35") (pinfunction "RESET(PDI_CLK)_35") (pintype "bidirectional"))
      (node (ref "R1") (pin "1") (pinfunction "1_1") (pintype "passive"))
      (node (ref "X1") (pin "5") (pinfunction "5_5") (pintype "passive"))
    )
    (net (code "55") (name "PDI-DATA") (class "Default")
      (node (ref "IC1") (pin "34") (pinfunction "PDI_34") (pintype "bidirectional"))
      (node (ref "X1") (pin "1") (pinfunction "1_1") (pintype "passive"))
    )
    (net (code "56") (name "RBUTTON") (class "Default")
      (node (ref "IC1") (pin "2") (pinfunction "PA6_2") (pintype "bidirectional"))
      (node (ref "RBTN") (pin "4") (pinfunction "4_4") (pintype "passive"))
    )
    (net (code "57") (name "RSSI") (class "Default")
      (node (ref "C32") (pin "1") (pinfunction "1_1") (pintype "passive"))
      (node (ref "IC1") (pin "41") (pinfunction "PA1_41") (pintype "bidirectional"))
      (node (ref "R10") (pin "2") (pinfunction "2_2") (pintype "passive"))
      (node (ref "R9") (pin "1") (pinfunction "1_1") (pintype "passive"))
    )
    (net (code "58") (name "SUBCARRIER-OOK{slash}MOD") (class "Default")
      (node (ref "IC1") (pin "15") (pinfunction "PC5_15") (pintype "bidirectional"))
      (node (ref "R18") (pin "2") (pinfunction "2_2") (pintype "passive"))
      (node (ref "R29") (pin "1") (pinfunction "1_1") (pintype "passive"))
      (node (ref "R30") (pin "2") (pinfunction "2_2") (pintype "passive"))
    )
    (net (code "59") (name "SUBCARRIER-PSK") (class "Default")
      (node (ref "IC1") (pin "14") (pinfunction "PC4_14") (pintype "bidirectional"))
      (node (ref "IC4") (pin "2") (pinfunction "I1_2") (pintype "input"))
    )
    (net (code "60") (name "USB-DM") (class "Default")
      (node (ref "IC1") (pin "26") (pinfunction "PD6_26") (pintype "bidirectional"))
      (node (ref "J1") (pin "D-") (pinfunction "D-_D-") (pintype "bidirectional"))
    )
    (net (code "61") (name "USB-DP") (class "Default")
      (node (ref "IC1") (pin "27") (pinfunction "PD7_27") (pintype "bidirectional"))
      (node (ref "J1") (pin "D+") (pinfunction "D+_D+") (pintype "bidirectional"))
    )
    (net (code "62") (name "USB-SENSE") (class "Default")
      (node (ref "IC1") (pin "25") (pinfunction "PD5_25") (pintype "bidirectional"))
      (node (ref "R2") (pin "1") (pinfunction "1_1") (pintype "passive"))
      (node (ref "R3") (pin "2") (pinfunction "2_2") (pintype "passive"))
    )
    (net (code "63") (name "VCC") (class "Default")
      (node (ref "C8") (pin "1") (pinfunction "1_1") (pintype "passive"))
      (node (ref "IC2") (pin "3") (pinfunction "IN_3") (pintype "input"))
      (node (ref "Q1") (pin "1") (pinfunction "S_1") (pintype "passive"))
      (node (ref "Q1") (pin "4") (pinfunction "S_4") (pintype "passive"))
      (node (ref "Q1") (pin "5") (pinfunction "G_5") (pintype "passive"))
      (node (ref "SW1") (pin "1") (pinfunction "O_1") (pintype "passive"))
    )
    (net (code "64") (name "unconnected-(IC1-PA0-Pad40)") (class "Default")
      (node (ref "IC1") (pin "40") (pinfunction "PA0_40") (pintype "bidirectional"))
    )
    (net (code "65") (name "unconnected-(IC1-PC3-Pad13)") (class "Default")
      (node (ref "IC1") (pin "13") (pinfunction "PC3_13") (pintype "bidirectional"))
    )
    (net (code "66") (name "unconnected-(IC1-PC7-Pad17)") (class "Default")
      (node (ref "IC1") (pin "17") (pinfunction "PC7_17") (pintype "bidirectional"))
    )
    (net (code "67") (name "unconnected-(IC1-PE1-Pad29)") (class "Default")
      (node (ref "IC1") (pin "29") (pinfunction "PE1_29") (pintype "bidirectional"))
    )
    (net (code "68") (name "unconnected-(LBUTTON-Pad2)") (class "Default")
      (node (ref "LBUTTON") (pin "2") (pinfunction "2_2") (pintype "passive"))
    )
    (net (code "69") (name "unconnected-(LBUTTON-Pad3)") (class "Default")
      (node (ref "LBUTTON") (pin "3") (pinfunction "3_3") (pintype "passive"))
    )
    (net (code "70") (name "unconnected-(RBTN-Pad2)") (class "Default")
      (node (ref "RBTN") (pin "2") (pinfunction "2_2") (pintype "passive"))
    )
    (net (code "71") (name "unconnected-(RBTN-Pad3)") (class "Default")
      (node (ref "RBTN") (pin "3") (pinfunction "3_3") (pintype "passive"))
    )
    (net (code "72") (name "unconnected-(X3-GND-PadGND2)") (class "Default")
      (node (ref "X3") (pin "GND2") (pinfunction "GND_GND2") (pintype "bidirectional"))
    )
    (net (code "73") (name "~{BRIDGE-CLK}") (class "Default")
      (node (ref "IC1") (pin "10") (pinfunction "PC0_10") (pintype "bidirectional"))
      (node (ref "IC7") (pin "1") (pinfunction "I0_1") (pintype "input"))
      (node (ref "R16") (pin "1") (pinfunction "1_1") (pintype "passive"))
    )
  )
)
